# 5V0_REG.net
KiCad netlist of a schematic drawn in Altium Designer
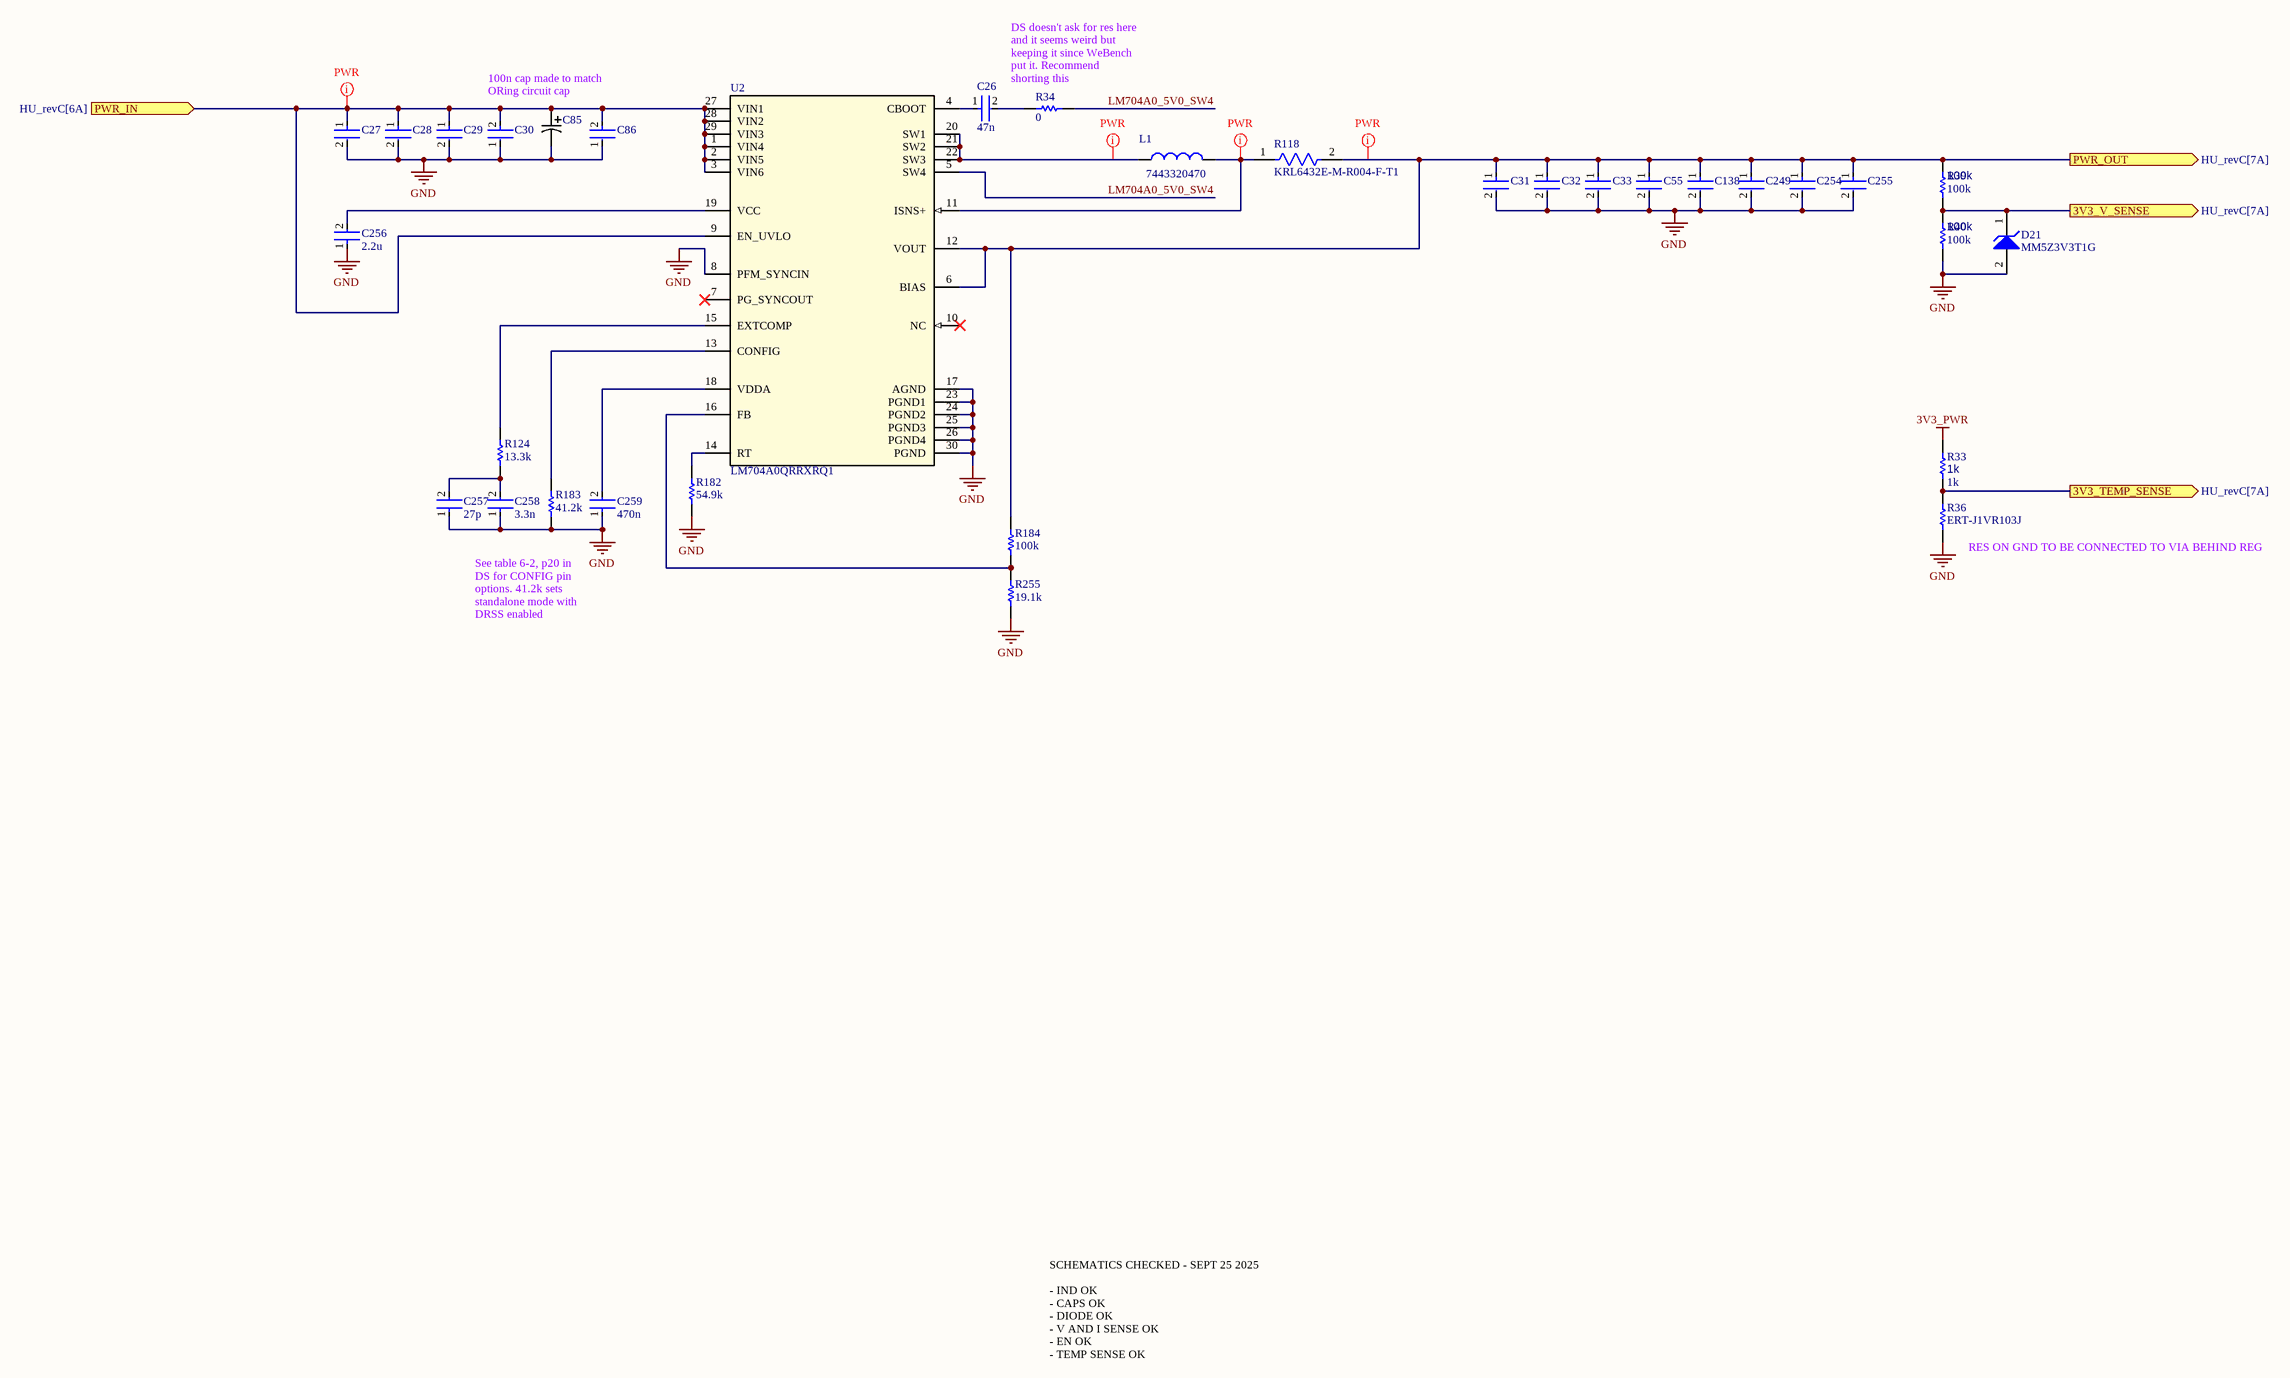
[diagram p0: 5V0_REG.SchDoc]

(export (version "E")
  (design (tool "Eeschema 10.0.6"))
  (components
    (comp (ref "C26")
      (value "47n")
      (footprint "FP-0402-L_1_0_0_05-W_0_5-IPC_A")
      (description "LARGE PADS, 0402 CAP, CHANGE COMMENT TO MATCH REAL P/N")
      (libsource (lib "Space Concordia") (part "b4654b650e69147ec39a6b967a45e02"))
    )
    (comp (ref "C27")
      (value "C3225X7R1H106M250AC")
      (footprint "FP-C3225-250-0_4-MFG")
      (description "Multilayer Ceramic Capacitors 10uF ±20% 50V X7R SMD 1210")
      (fields (field (name "TOLERANCE") "20%"))
      (libsource (lib "Altium Content Vault") (part "02cd4be3c70576c341d710602a673aa"))
    )
    (comp (ref "C28")
      (value "C3225X7R1H106M250AC")
      (footprint "FP-C3225-250-0_4-MFG")
      (description "Multilayer Ceramic Capacitors 10uF ±20% 50V X7R SMD 1210")
      (fields (field (name "TOLERANCE") "20%"))
      (libsource (lib "Altium Content Vault") (part "02cd4be3c70576c341d710602a673aa"))
    )
    (comp (ref "C29")
      (value "C3225X7R1H106M250AC")
      (footprint "FP-C3225-250-0_4-MFG")
      (description "Multilayer Ceramic Capacitors 10uF ±20% 50V X7R SMD 1210")
      (fields (field (name "TOLERANCE") "20%"))
      (libsource (lib "Altium Content Vault") (part "02cd4be3c70576c341d710602a673aa"))
    )
    (comp (ref "C30")
      (value "AC1210KKX7R0BB104")
      (footprint "FP-AC1210-0_85-MFG")
      (description "CAP CER 0.1UF 100V X7R 1210")
      (fields (field (name "MANUFACTURER") "Yageo") (field (name "TOLERANCE") "0.1"))
      (libsource (lib "Altium Content Vault") (part "236180d848d6139a670b325ea6854c9"))
    )
    (comp (ref "C31")
      (value "GRM32ER61C476KE15L")
      (footprint "FP-GRM32E-0_3-0_2-IPC_C")
      (description "CAP CER 47UF 16V X5R 1210")
      (fields (field (name "VOLTAGE") "16V") (field (name "TOLERANCE") "10%"))
      (libsource (lib "Altium Content Vault") (part "b4654b650e69147ec39a6b967a45e02"))
    )
    (comp (ref "C32")
      (value "GRM32ER61C476KE15L")
      (footprint "FP-GRM32E-0_3-0_2-IPC_C")
      (description "CAP CER 47UF 16V X5R 1210")
      (fields (field (name "VOLTAGE") "16V") (field (name "TOLERANCE") "10%"))
      (libsource (lib "Altium Content Vault") (part "b4654b650e69147ec39a6b967a45e02"))
    )
    (comp (ref "C33")
      (value "GRM32ER61C476KE15L")
      (footprint "FP-GRM32E-0_3-0_2-IPC_C")
      (description "CAP CER 47UF 16V X5R 1210")
      (fields (field (name "VOLTAGE") "16V") (field (name "TOLERANCE") "10%"))
      (libsource (lib "Altium Content Vault") (part "b4654b650e69147ec39a6b967a45e02"))
    )
    (comp (ref "C55")
      (value "GRM32ER61C476KE15L")
      (footprint "FP-GRM32E-0_3-0_2-IPC_C")
      (description "CAP CER 47UF 16V X5R 1210")
      (fields (field (name "VOLTAGE") "16V") (field (name "TOLERANCE") "10%"))
      (libsource (lib "Altium Content Vault") (part "b4654b650e69147ec39a6b967a45e02"))
    )
    (comp (ref "C85")
      (value "DNP")
      (footprint "T495D337K010ATE150-Footprint-1")
      (description "T495X107K020ATE150 diff p/n")
      (fields (field (name "TOLERANCE") "10%"))
      (libsource (lib "Space Concordia") (part "T495D337K010ATE150"))
    )
    (comp (ref "C86")
      (value "AC1210KKX7R0BB104")
      (footprint "FP-AC1210-0_85-MFG")
      (description "CAP CER 0.1UF 100V X7R 1210")
      (fields (field (name "MANUFACTURER") "Yageo") (field (name "TOLERANCE") "0.1"))
      (libsource (lib "Altium Content Vault") (part "236180d848d6139a670b325ea6854c9"))
    )
    (comp (ref "C138")
      (value "GRM32ER61C476KE15L")
      (footprint "FP-GRM32E-0_3-0_2-IPC_C")
      (description "CAP CER 47UF 16V X5R 1210")
      (fields (field (name "VOLTAGE") "16V") (field (name "TOLERANCE") "10%"))
      (libsource (lib "Altium Content Vault") (part "b4654b650e69147ec39a6b967a45e02"))
    )
    (comp (ref "C249")
      (value "GRM32ER61C476KE15L")
      (footprint "FP-GRM32E-0_3-0_2-IPC_C")
      (description "CAP CER 47UF 16V X5R 1210")
      (fields (field (name "VOLTAGE") "16V") (field (name "TOLERANCE") "10%"))
      (libsource (lib "Altium Content Vault") (part "b4654b650e69147ec39a6b967a45e02"))
    )
    (comp (ref "C254")
      (value "GRM32ER61C476KE15L")
      (footprint "FP-GRM32E-0_3-0_2-IPC_C")
      (description "CAP CER 47UF 16V X5R 1210")
      (fields (field (name "VOLTAGE") "16V") (field (name "TOLERANCE") "10%"))
      (libsource (lib "Altium Content Vault") (part "b4654b650e69147ec39a6b967a45e02"))
    )
    (comp (ref "C255")
      (value "GRM32ER61C476KE15L")
      (footprint "FP-GRM32E-0_3-0_2-IPC_C")
      (description "CAP CER 47UF 16V X5R 1210")
      (fields (field (name "VOLTAGE") "16V") (field (name "TOLERANCE") "10%"))
      (libsource (lib "Altium Content Vault") (part "b4654b650e69147ec39a6b967a45e02"))
    )
    (comp (ref "C256")
      (value "2.2u")
      (footprint "FP-0402-L_1_0_0_05-W_0_5-IPC_A")
      (description "LARGE PADS, 0402 CAP, CHANGE COMMENT TO MATCH REAL P/N")
      (libsource (lib "Space Concordia") (part "b4654b650e69147ec39a6b967a45e02"))
    )
    (comp (ref "C257")
      (value "27p")
      (footprint "FP-0402-L_1_0_0_05-W_0_5-IPC_A")
      (description "LARGE PADS, 0402 CAP, CHANGE COMMENT TO MATCH REAL P/N")
      (libsource (lib "Space Concordia") (part "b4654b650e69147ec39a6b967a45e02"))
    )
    (comp (ref "C258")
      (value "3.3n")
      (footprint "FP-0402-L_1_0_0_05-W_0_5-IPC_A")
      (description "LARGE PADS, 0402 CAP, CHANGE COMMENT TO MATCH REAL P/N")
      (libsource (lib "Space Concordia") (part "b4654b650e69147ec39a6b967a45e02"))
    )
    (comp (ref "C259")
      (value "470n")
      (footprint "FP-0402-L_1_0_0_05-W_0_5-IPC_A")
      (description "LARGE PADS, 0402 CAP, CHANGE COMMENT TO MATCH REAL P/N")
      (libsource (lib "Space Concordia") (part "b4654b650e69147ec39a6b967a45e02"))
    )
    (comp (ref "D21")
      (value "MM5Z3V3T1G")
      (footprint "ONSC-SOD-523-2-502-01_V")
      (description "Zener Voltage Regulator, 500 mW, 2-Pin SOD-523, Pb-Free, Tape and Reel")
      (fields (field (name "MANUFACTURER") "On Semiconductor"))
      (libsource (lib "Altium Content Vault") (part "ONSC-K1A2-2"))
    )
    (comp (ref "L1")
      (value "7443320470")
      (footprint "WE-HCC_1210")
      (description "We-hcc Series, Shielded Wire-wound SMD Inductor With Ferrite Core, 4.7 Uh")
      (libsource (lib "Altium Content Vault") (part "Inductor - 1"))
    )
    (comp (ref "R33")
      (value "1k")
      (footprint "R0603B")
      (description "Resistor")
      (fields (field (name "ALTIUM_VALUE") "1k"))
      (libsource (lib "Space Concordia") (part "Resistor"))
    )
    (comp (ref "R34")
      (value "0")
      (footprint "R0603B")
      (description "Resistor")
      (libsource (lib "Space Concordia") (part "Resistor"))
    )
    (comp (ref "R36")
      (value "ERT-J1VR103J")
      (footprint "RESC1608X90X30ML15T20")
      (fields (field (name "MANUFACTURER") "Panasonic"))
      (libsource (lib "Altium Content Vault") (part "RES"))
    )
    (comp (ref "R39")
      (value "100k")
      (footprint "R0603B")
      (description "Resistor")
      (fields (field (name "ALTIUM_VALUE") "100k"))
      (libsource (lib "Space Concordia") (part "Resistor"))
    )
    (comp (ref "R40")
      (value "100k")
      (footprint "R0603B")
      (description "Resistor")
      (fields (field (name "ALTIUM_VALUE") "100k"))
      (libsource (lib "Space Concordia") (part "Resistor"))
    )
    (comp (ref "R118")
      (value "KRL6432E-M-R004-F-T1")
      (footprint "FP-KRL6432E-MFG")
      (description "KRL6432E-M-R004-F-T1 Metal Foil Low Resistance Chip Resistor (long-side terminal), 2512, RoHS")
      (fields (field (name "TOLERANCE") "1%"))
      (libsource (lib "Altium Content Vault") (part "1029c3af85768c4190bb7ad29bc67b5"))
    )
    (comp (ref "R124")
      (value "13.3k")
      (footprint "R0603B")
      (description "Resistor")
      (libsource (lib "Space Concordia") (part "Resistor"))
    )
    (comp (ref "R182")
      (value "54.9k")
      (footprint "R0603B")
      (description "Resistor")
      (libsource (lib "Space Concordia") (part "Resistor"))
    )
    (comp (ref "R183")
      (value "41.2k")
      (footprint "R0603B")
      (description "Resistor")
      (libsource (lib "Space Concordia") (part "Resistor"))
    )
    (comp (ref "R184")
      (value "100k")
      (footprint "R0603B")
      (description "Resistor")
      (libsource (lib "Space Concordia") (part "Resistor"))
    )
    (comp (ref "R255")
      (value "19.1k")
      (footprint "R0603B")
      (description "Resistor")
      (libsource (lib "Space Concordia") (part "Resistor"))
    )
    (comp (ref "U2")
      (value "LM704A0QRRXRQ1")
      (footprint "LM704A0QRRXRQ1-Footprint-1")
      (libsource (lib "Space Concordia") (part "LM704A0QRRXRQ1"))
    )
  )
  (nets
    (net (code "1") (name "/3V3_TEMP_SENSE") (class "Default")
      (node (ref "R33") (pin "2") (pinfunction "2_2") (pintype "passive"))
      (node (ref "R36") (pin "2") (pinfunction "2_2") (pintype "passive"))
    )
    (net (code "2") (name "/3V3_V_SENSE") (class "Default")
      (node (ref "D21") (pin "1") (pinfunction "K_1") (pintype "passive"))
      (node (ref "R39") (pin "1") (pinfunction "1_1") (pintype "passive"))
      (node (ref "R40") (pin "2") (pinfunction "2_2") (pintype "passive"))
    )
    (net (code "3") (name "/LM704A0_5V0_SW4") (class "Default")
      (node (ref "R34") (pin "2") (pinfunction "2_2") (pintype "passive"))
      (node (ref "U2") (pin "5") (pinfunction "SW4_5") (pintype "power_in"))
    )
    (net (code "4") (name "/PWR_IN") (class "Default")
      (node (ref "C27") (pin "1") (pinfunction "1_1") (pintype "passive"))
      (node (ref "C28") (pin "1") (pinfunction "1_1") (pintype "passive"))
      (node (ref "C29") (pin "1") (pinfunction "1_1") (pintype "passive"))
      (node (ref "C30") (pin "2") (pinfunction "2_2") (pintype "passive"))
      (node (ref "C85") (pin "1") (pinfunction "1_1") (pintype "passive"))
      (node (ref "C86") (pin "2") (pinfunction "2_2") (pintype "passive"))
      (node (ref "U2") (pin "1") (pinfunction "VIN4_1") (pintype "passive"))
      (node (ref "U2") (pin "2") (pinfunction "VIN5_2") (pintype "passive"))
      (node (ref "U2") (pin "27") (pinfunction "VIN1_27") (pintype "power_in"))
      (node (ref "U2") (pin "28") (pinfunction "VIN2_28") (pintype "power_in"))
      (node (ref "U2") (pin "29") (pinfunction "VIN3_29") (pintype "power_in"))
      (node (ref "U2") (pin "3") (pinfunction "VIN6_3") (pintype "power_in"))
      (node (ref "U2") (pin "9") (pinfunction "EN_UVLO_9") (pintype "open_collector"))
    )
    (net (code "5") (name "/PWR_OUT") (class "Default")
      (node (ref "C138") (pin "1") (pinfunction "1_1") (pintype "passive"))
      (node (ref "C249") (pin "1") (pinfunction "1_1") (pintype "passive"))
      (node (ref "C254") (pin "1") (pinfunction "1_1") (pintype "passive"))
      (node (ref "C255") (pin "1") (pinfunction "1_1") (pintype "passive"))
      (node (ref "C31") (pin "1") (pinfunction "1_1") (pintype "passive"))
      (node (ref "C32") (pin "1") (pinfunction "1_1") (pintype "passive"))
      (node (ref "C33") (pin "1") (pinfunction "1_1") (pintype "passive"))
      (node (ref "C55") (pin "1") (pinfunction "1_1") (pintype "passive"))
      (node (ref "R118") (pin "2") (pinfunction "2_2") (pintype "passive"))
      (node (ref "R184") (pin "1") (pinfunction "1_1") (pintype "passive"))
      (node (ref "R39") (pin "2") (pinfunction "2_2") (pintype "passive"))
      (node (ref "U2") (pin "12") (pinfunction "VOUT_12") (pintype "passive"))
      (node (ref "U2") (pin "6") (pinfunction "BIAS_6") (pintype "passive"))
    )
    (net (code "6") (name "3V3_PWR") (class "Default")
      (node (ref "R33") (pin "1") (pinfunction "1_1") (pintype "passive"))
    )
    (net (code "7") (name "GND") (class "Default")
      (node (ref "C138") (pin "2") (pinfunction "2_2") (pintype "passive"))
      (node (ref "C249") (pin "2") (pinfunction "2_2") (pintype "passive"))
      (node (ref "C254") (pin "2") (pinfunction "2_2") (pintype "passive"))
      (node (ref "C255") (pin "2") (pinfunction "2_2") (pintype "passive"))
      (node (ref "C256") (pin "1") (pinfunction "1_1") (pintype "passive"))
      (node (ref "C257") (pin "1") (pinfunction "1_1") (pintype "passive"))
      (node (ref "C258") (pin "1") (pinfunction "1_1") (pintype "passive"))
      (node (ref "C259") (pin "1") (pinfunction "1_1") (pintype "passive"))
      (node (ref "C27") (pin "2") (pinfunction "2_2") (pintype "passive"))
      (node (ref "C28") (pin "2") (pinfunction "2_2") (pintype "passive"))
      (node (ref "C29") (pin "2") (pinfunction "2_2") (pintype "passive"))
      (node (ref "C30") (pin "1") (pinfunction "1_1") (pintype "passive"))
      (node (ref "C31") (pin "2") (pinfunction "2_2") (pintype "passive"))
      (node (ref "C32") (pin "2") (pinfunction "2_2") (pintype "passive"))
      (node (ref "C33") (pin "2") (pinfunction "2_2") (pintype "passive"))
      (node (ref "C55") (pin "2") (pinfunction "2_2") (pintype "passive"))
      (node (ref "C85") (pin "2") (pinfunction "2_2") (pintype "passive"))
      (node (ref "C86") (pin "1") (pinfunction "1_1") (pintype "passive"))
      (node (ref "D21") (pin "2") (pinfunction "A_2") (pintype "passive"))
      (node (ref "R182") (pin "2") (pinfunction "2_2") (pintype "passive"))
      (node (ref "R183") (pin "2") (pinfunction "2_2") (pintype "passive"))
      (node (ref "R255") (pin "2") (pinfunction "2_2") (pintype "passive"))
      (node (ref "R36") (pin "1") (pinfunction "1_1") (pintype "passive"))
      (node (ref "R40") (pin "1") (pinfunction "1_1") (pintype "passive"))
      (node (ref "U2") (pin "17") (pinfunction "AGND_17") (pintype "passive"))
      (node (ref "U2") (pin "23") (pinfunction "PGND1_23") (pintype "passive"))
      (node (ref "U2") (pin "24") (pinfunction "PGND2_24") (pintype "passive"))
      (node (ref "U2") (pin "25") (pinfunction "PGND3_25") (pintype "power_in"))
      (node (ref "U2") (pin "26") (pinfunction "PGND4_26") (pintype "power_in"))
      (node (ref "U2") (pin "30") (pinfunction "PGND_30") (pintype "power_in"))
      (node (ref "U2") (pin "8") (pinfunction "PFM_SYNCIN_8") (pintype "power_in"))
    )
    (net (code "8") (name "Net-(C26-Pad2)") (class "Default")
      (node (ref "C26") (pin "2") (pinfunction "2_2") (pintype "passive"))
      (node (ref "R34") (pin "1") (pinfunction "1_1") (pintype "passive"))
    )
    (net (code "9") (name "Net-(C257-Pad2)") (class "Default")
      (node (ref "C257") (pin "2") (pinfunction "2_2") (pintype "passive"))
      (node (ref "C258") (pin "2") (pinfunction "2_2") (pintype "passive"))
      (node (ref "R124") (pin "1") (pinfunction "1_1") (pintype "passive"))
    )
    (net (code "10") (name "Net-(U2-CBOOT)") (class "Default")
      (node (ref "C26") (pin "1") (pinfunction "1_1") (pintype "passive"))
      (node (ref "U2") (pin "4") (pinfunction "CBOOT_4") (pintype "power_in"))
    )
    (net (code "11") (name "Net-(U2-CONFIG)") (class "Default")
      (node (ref "R183") (pin "1") (pinfunction "1_1") (pintype "passive"))
      (node (ref "U2") (pin "13") (pinfunction "CONFIG_13") (pintype "passive"))
    )
    (net (code "12") (name "Net-(U2-EXTCOMP)") (class "Default")
      (node (ref "R124") (pin "2") (pinfunction "2_2") (pintype "passive"))
      (node (ref "U2") (pin "15") (pinfunction "EXTCOMP_15") (pintype "passive"))
    )
    (net (code "13") (name "Net-(U2-FB)") (class "Default")
      (node (ref "R184") (pin "2") (pinfunction "2_2") (pintype "passive"))
      (node (ref "R255") (pin "1") (pinfunction "1_1") (pintype "passive"))
      (node (ref "U2") (pin "16") (pinfunction "FB_16") (pintype "passive"))
    )
    (net (code "14") (name "Net-(U2-ISNS+)") (class "Default")
      (node (ref "L1") (pin "2") (pinfunction "2_2") (pintype "passive"))
      (node (ref "R118") (pin "1") (pinfunction "1_1") (pintype "passive"))
      (node (ref "U2") (pin "11") (pinfunction "ISNS+_11") (pintype "input"))
    )
    (net (code "15") (name "Net-(U2-RT)") (class "Default")
      (node (ref "R182") (pin "1") (pinfunction "1_1") (pintype "passive"))
      (node (ref "U2") (pin "14") (pinfunction "RT_14") (pintype "passive"))
    )
    (net (code "16") (name "Net-(U2-SW1)") (class "Default")
      (node (ref "L1") (pin "1") (pinfunction "1_1") (pintype "passive"))
      (node (ref "U2") (pin "20") (pinfunction "SW1_20") (pintype "power_in"))
      (node (ref "U2") (pin "21") (pinfunction "SW2_21") (pintype "power_in"))
      (node (ref "U2") (pin "22") (pinfunction "SW3_22") (pintype "passive"))
    )
    (net (code "17") (name "Net-(U2-VCC)") (class "Default")
      (node (ref "C256") (pin "2") (pinfunction "2_2") (pintype "passive"))
      (node (ref "U2") (pin "19") (pinfunction "VCC_19") (pintype "power_in"))
    )
    (net (code "18") (name "Net-(U2-VDDA)") (class "Default")
      (node (ref "C259") (pin "2") (pinfunction "2_2") (pintype "passive"))
      (node (ref "U2") (pin "18") (pinfunction "VDDA_18") (pintype "passive"))
    )
    (net (code "19") (name "unconnected-(U2-NC-Pad10)") (class "Default")
      (node (ref "U2") (pin "10") (pinfunction "NC_10") (pintype "input+no_connect"))
    )
    (net (code "20") (name "unconnected-(U2-PG_SYNCOUT-Pad7)") (class "Default")
      (node (ref "U2") (pin "7") (pinfunction "PG_SYNCOUT_7") (pintype "passive+no_connect"))
    )
  )
)
